# sapflow_v3.net
KiCad netlist of a schematic drawn in EAGLE
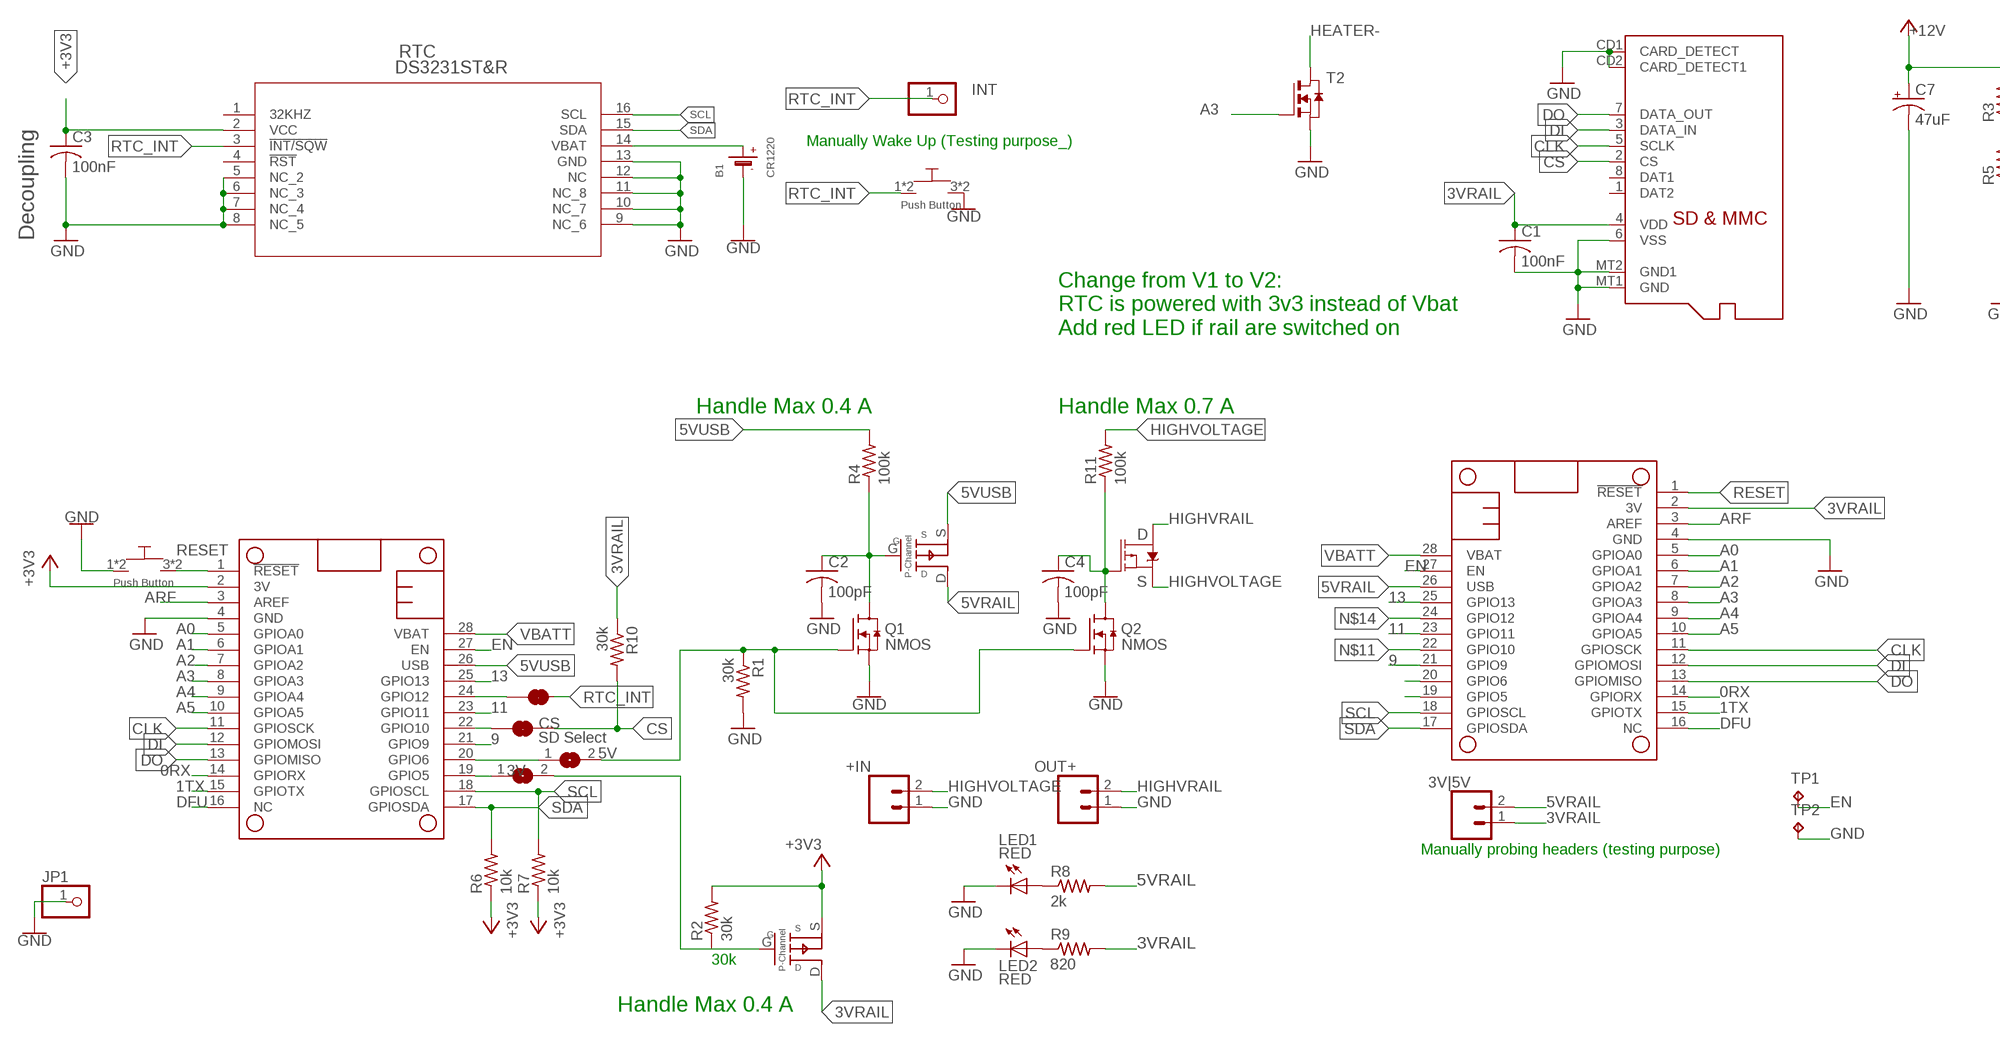
[diagram p0: schematic, sheet 1, part 1 of 2]
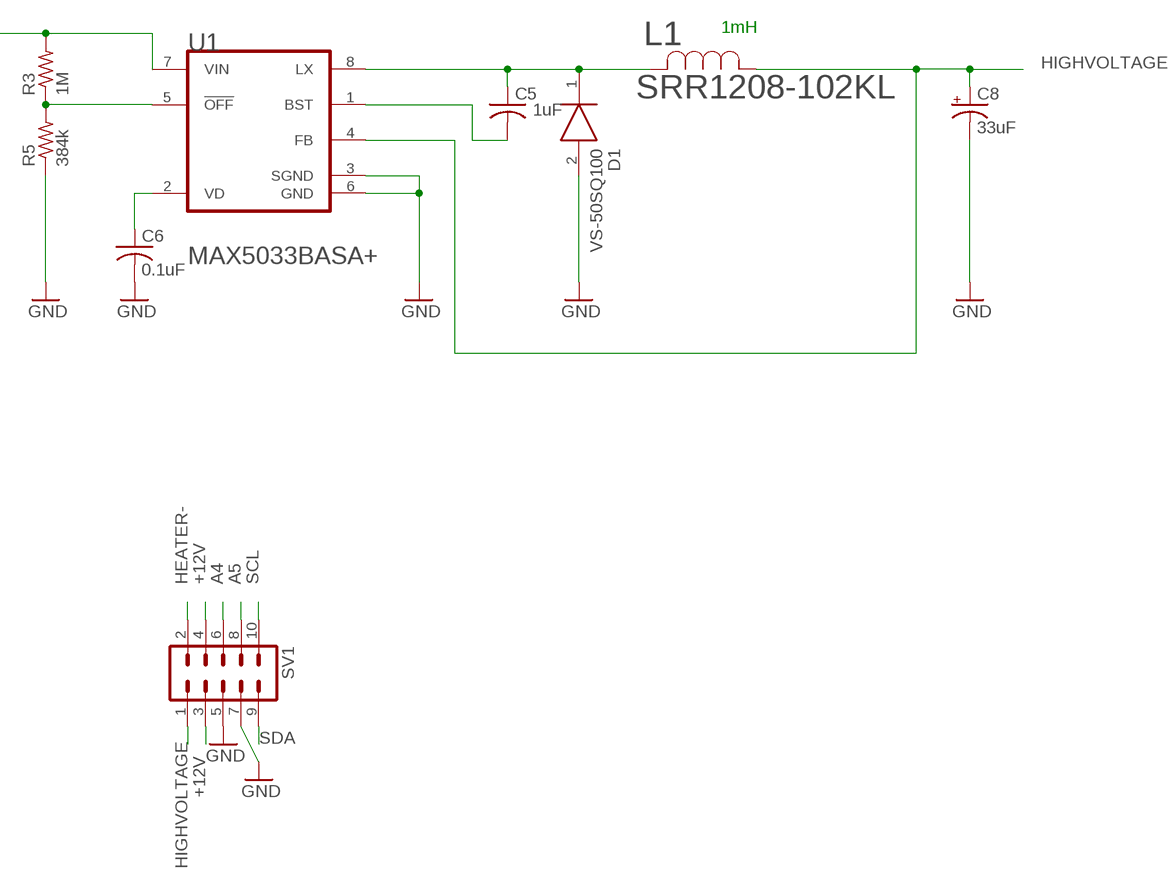
[diagram p1: schematic, sheet 1, part 2 of 2]

(export (version "E")
  (design (tool "Eeschema 10.0.6"))
  (components
    (comp (ref "+IN")
      (value "HIGHV-IN")
      (footprint "eagle-import:1X02_NO_SILK")
      (libsource (lib "eagle-import") (part "CONN_021X02_NO_SILK"))
    )
    (comp (ref "3V") (value "SJ") (footprint "eagle-import:SJ") (libsource (lib "eagle-import") (part "SJ")))
    (comp (ref "3V|5V")
      (value "CONN_021X02_NO_SILK")
      (footprint "eagle-import:1X02_NO_SILK")
      (libsource (lib "eagle-import") (part "CONN_021X02_NO_SILK"))
    )
    (comp (ref "5V") (value "SJ") (footprint "eagle-import:SJ") (libsource (lib "eagle-import") (part "SJ")))
    (comp (ref "B1")
      (value "CR1220")
      (footprint "eagle-import:CR1220")
      (libsource (lib "eagle-import") (part "BATTERYCR1220_SMT"))
    )
    (comp (ref "C1")
      (value "100nF")
      (footprint "eagle-import:C1206")
      (libsource (lib "eagle-import") (part "C-USC1206"))
    )
    (comp (ref "C2")
      (value "100pF")
      (footprint "eagle-import:C0805")
      (libsource (lib "eagle-import") (part "resistor_348_C-USC0805"))
    )
    (comp (ref "C3")
      (value "100nF")
      (footprint "eagle-import:C1206")
      (libsource (lib "eagle-import") (part "C-USC1206"))
    )
    (comp (ref "C4")
      (value "100pF")
      (footprint "eagle-import:C0805")
      (libsource (lib "eagle-import") (part "resistor_348_C-USC0805"))
    )
    (comp (ref "C5")
      (value "1uF")
      (footprint "eagle-import:C0603")
      (libsource (lib "eagle-import") (part "rcl_334_C-USC0603"))
    )
    (comp (ref "C6")
      (value "0.1uF")
      (footprint "eagle-import:C0603")
      (libsource (lib "eagle-import") (part "rcl_334_C-USC0603"))
    )
    (comp (ref "C7")
      (value "47uF")
      (footprint "eagle-import:D_7343-31R")
      (libsource (lib "eagle-import") (part "CPOL-USD/7343-31R"))
    )
    (comp (ref "C8")
      (value "33uF")
      (footprint "eagle-import:D_7343-31R")
      (libsource (lib "eagle-import") (part "CPOL-USD/7343-31R"))
    )
    (comp (ref "CS")
      (value "SD Select")
      (footprint "eagle-import:SMT-JUMPER_2_NC_TRACE_SILK")
      (libsource (lib "eagle-import") (part "JUMPER-SMT_2_NC_TRACE_SILK"))
    )
    (comp (ref "D1")
      (value "VS-50SQ100")
      (footprint "eagle-import:DIOAD1405W86L465D235")
      (fields (field (name "MOUSER_PART_NUMBER") "844-50SQ100") (field (name "RS_PART_NUMBER") "5446041"))
      (libsource (lib "eagle-import") (part "VS-50SQ100"))
    )
    (comp (ref "INT")
      (value "PINHD-1X1CB")
      (footprint "eagle-import:1X01-CLEANBIG")
      (libsource (lib "eagle-import") (part "PINHD-1X1CB"))
    )
    (comp (ref "JP1")
      (value "PINHD-1X1CB")
      (footprint "eagle-import:1X01-CLEANBIG")
      (libsource (lib "eagle-import") (part "PINHD-1X1CB"))
    )
    (comp (ref "L1")
      (value "SRR1208-102KL")
      (footprint "eagle-import:IND_BOURNS_SRR1208")
      (libsource (lib "eagle-import") (part "SRR1208-102KL"))
    )
    (comp (ref "LED1")
      (value "RED")
      (footprint "eagle-import:CHIPLED_0805")
      (libsource (lib "eagle-import") (part "LEDCHIPLED_0805"))
    )
    (comp (ref "LED2")
      (value "RED")
      (footprint "eagle-import:CHIPLED_0805")
      (libsource (lib "eagle-import") (part "LEDCHIPLED_0805"))
    )
    (comp (ref "MICROSD")
      (value "MICROSD")
      (footprint "eagle-import:MICROSD")
      (libsource (lib "eagle-import") (part "MICROSD"))
    )
    (comp (ref "MS1")
      (value "FEATHERWING")
      (footprint "eagle-import:FEATHERWING")
      (libsource (lib "eagle-import") (part "powerboard_FEATHERWING"))
    )
    (comp (ref "MS2")
      (value "FEATHERWING")
      (footprint "eagle-import:FEATHERWING")
      (libsource (lib "eagle-import") (part "FEATHERWING"))
    )
    (comp (ref "OUT+")
      (value "HIGHV-OUT")
      (footprint "eagle-import:1X02_NO_SILK")
      (libsource (lib "eagle-import") (part "CONN_021X02_NO_SILK"))
    )
    (comp (ref "PMOS1")
      (value "SSM3J3228R")
      (footprint "eagle-import:SOT-23-3")
      (libsource (lib "eagle-import") (part "SSM3J3228R"))
    )
    (comp (ref "PMOS2")
      (value "SSM3J3228R")
      (footprint "eagle-import:SOT-23-3")
      (libsource (lib "eagle-import") (part "SSM3J3228R"))
    )
    (comp (ref "PMOS3")
      (value "P-MOSFET")
      (footprint "eagle-import:SOT23-6")
      (libsource (lib "eagle-import") (part "P-MOSFET"))
    )
    (comp (ref "Q1")
      (value "NMOS")
      (footprint "eagle-import:SOT23-S")
      (libsource (lib "eagle-import") (part "NMOS"))
    )
    (comp (ref "Q2")
      (value "NMOS")
      (footprint "eagle-import:SOT23-S")
      (libsource (lib "eagle-import") (part "NMOS"))
    )
    (comp (ref "R1")
      (value "30k")
      (footprint "eagle-import:RES_1206")
      (fields
        (field (name "DIGIKEY_PART_NUMBER") "WSLP-.05TR-ND")
        (field (name "MANUFACTURER") "Vishay Dale")
        (field (name "MPN") "WSLP1206R0500FEA")
        (field (name "CREATED_BY") "PCBLayout.com")
      )
      (libsource (lib "eagle-import") (part "WSLP1206R0500FEA"))
    )
    (comp (ref "R2")
      (value "30k")
      (footprint "eagle-import:RES_1206")
      (fields
        (field (name "DIGIKEY_PART_NUMBER") "WSLP-.05TR-ND")
        (field (name "MANUFACTURER") "Vishay Dale")
        (field (name "MPN") "WSLP1206R0500FEA")
        (field (name "CREATED_BY") "PCBLayout.com")
      )
      (libsource (lib "eagle-import") (part "WSLP1206R0500FEA"))
    )
    (comp (ref "R3")
      (value "1M")
      (footprint "eagle-import:R0603")
      (libsource (lib "eagle-import") (part "R-US_R0603"))
    )
    (comp (ref "R4")
      (value "100k")
      (footprint "eagle-import:RES_1206")
      (fields
        (field (name "DIGIKEY_PART_NUMBER") "WSLP-.05TR-ND")
        (field (name "MANUFACTURER") "Vishay Dale")
        (field (name "MPN") "WSLP1206R0500FEA")
        (field (name "CREATED_BY") "PCBLayout.com")
      )
      (libsource (lib "eagle-import") (part "WSLP1206R0500FEA"))
    )
    (comp (ref "R5")
      (value "384k")
      (footprint "eagle-import:R0603")
      (libsource (lib "eagle-import") (part "R-US_R0603"))
    )
    (comp (ref "R6")
      (value "10k")
      (footprint "eagle-import:RES_1206")
      (fields
        (field (name "DIGIKEY_PART_NUMBER") "WSLP-.05TR-ND")
        (field (name "MANUFACTURER") "Vishay Dale")
        (field (name "MPN") "WSLP1206R0500FEA")
        (field (name "CREATED_BY") "PCBLayout.com")
      )
      (libsource (lib "eagle-import") (part "WSLP1206R0500FEA"))
    )
    (comp (ref "R7")
      (value "10k")
      (footprint "eagle-import:RES_1206")
      (fields
        (field (name "DIGIKEY_PART_NUMBER") "WSLP-.05TR-ND")
        (field (name "MANUFACTURER") "Vishay Dale")
        (field (name "MPN") "WSLP1206R0500FEA")
        (field (name "CREATED_BY") "PCBLayout.com")
      )
      (libsource (lib "eagle-import") (part "WSLP1206R0500FEA"))
    )
    (comp (ref "R8")
      (value "2k")
      (footprint "eagle-import:RES_1206")
      (fields
        (field (name "DIGIKEY_PART_NUMBER") "WSLP-.05TR-ND")
        (field (name "MANUFACTURER") "Vishay Dale")
        (field (name "MPN") "WSLP1206R0500FEA")
        (field (name "CREATED_BY") "PCBLayout.com")
      )
      (libsource (lib "eagle-import") (part "WSLP1206R0500FEA"))
    )
    (comp (ref "R9")
      (value "820")
      (footprint "eagle-import:RES_1206")
      (fields
        (field (name "DIGIKEY_PART_NUMBER") "WSLP-.05TR-ND")
        (field (name "MANUFACTURER") "Vishay Dale")
        (field (name "MPN") "WSLP1206R0500FEA")
        (field (name "CREATED_BY") "PCBLayout.com")
      )
      (libsource (lib "eagle-import") (part "WSLP1206R0500FEA"))
    )
    (comp (ref "R10")
      (value "30k")
      (footprint "eagle-import:RES_1206")
      (fields
        (field (name "DIGIKEY_PART_NUMBER") "WSLP-.05TR-ND")
        (field (name "MANUFACTURER") "Vishay Dale")
        (field (name "MPN") "WSLP1206R0500FEA")
        (field (name "CREATED_BY") "PCBLayout.com")
      )
      (libsource (lib "eagle-import") (part "WSLP1206R0500FEA"))
    )
    (comp (ref "R11")
      (value "100k")
      (footprint "eagle-import:RES_1206")
      (fields
        (field (name "DIGIKEY_PART_NUMBER") "WSLP-.05TR-ND")
        (field (name "MANUFACTURER") "Vishay Dale")
        (field (name "MPN") "WSLP1206R0500FEA")
        (field (name "CREATED_BY") "PCBLayout.com")
      )
      (libsource (lib "eagle-import") (part "WSLP1206R0500FEA"))
    )
    (comp (ref "RTC")
      (value "DS3231ST&R")
      (footprint "eagle-import:21-0042B_16")
      (fields (field (name "MANUFACTURER_PART_NUMBER") "DS3231S#T&R"))
      (libsource (lib "eagle-import") (part "DS3231ST&R"))
    )
    (comp (ref "RTC_INT")
      (value "JUMPER-SMT_2_NC_TRACE_SILK")
      (footprint "eagle-import:SMT-JUMPER_2_NC_TRACE_SILK")
      (libsource (lib "eagle-import") (part "JUMPER-SMT_2_NC_TRACE_SILK"))
    )
    (comp (ref "SV1")
      (value "MA05-2")
      (footprint "eagle-import:MA05-2")
      (libsource (lib "eagle-import") (part "MA05-2"))
    )
    (comp (ref "T2")
      (value "NMOSSOT223")
      (footprint "eagle-import:SOT223")
      (libsource (lib "eagle-import") (part "NMOSSOT223"))
    )
    (comp (ref "TP1")
      (value "TPTP16R")
      (footprint "eagle-import:TP16R")
      (libsource (lib "eagle-import") (part "TPTP16R"))
    )
    (comp (ref "TP2")
      (value "TPTP16R")
      (footprint "eagle-import:TP16R")
      (libsource (lib "eagle-import") (part "TPTP16R"))
    )
    (comp (ref "U$1")
      (value "PUSH_BUTTON")
      (footprint "eagle-import:PUSHBUTTON_SMD")
      (libsource (lib "eagle-import") (part "PUSH_BUTTON"))
    )
    (comp (ref "U$2")
      (value "PUSH_BUTTON")
      (footprint "eagle-import:PUSHBUTTON_SMD")
      (libsource (lib "eagle-import") (part "PUSH_BUTTON"))
    )
    (comp (ref "U1")
      (value "MAXIM_MAX5033BASA+MAXIM_MAX5033BASA+_0_1")
      (footprint "eagle-import:MAXIM_MAX5033BASA+_1")
      (fields (field (name "MF") "Maxim") (field (name "MPN") "MAX5033BASA+"))
      (libsource (lib "eagle-import") (part "MAXIM_MAX5033BASA+MAXIM_MAX5033BASA+_0_1"))
    )
  )
  (nets
    (net (code "1") (name "+3V3") (class "Default")
      (node (ref "C3") (pin "1") (pinfunction "1_1") (pintype "passive"))
      (node (ref "MS2") (pin "2") (pinfunction "3V_2") (pintype "power_in"))
      (node (ref "PMOS2") (pin "S") (pinfunction "S_S") (pintype "bidirectional"))
      (node (ref "R2") (pin "2") (pinfunction "2_2") (pintype "passive"))
      (node (ref "R6") (pin "1") (pinfunction "1_1") (pintype "passive"))
      (node (ref "R7") (pin "1") (pinfunction "1_1") (pintype "passive"))
      (node (ref "RTC") (pin "2") (pinfunction "VCC_2") (pintype "power_in"))
    )
    (net (code "2") (name "/0RX") (class "Default")
      (node (ref "MS1") (pin "14") (pinfunction "GPIORX_14") (pintype "bidirectional"))
      (node (ref "MS2") (pin "14") (pinfunction "GPIORX_14") (pintype "bidirectional"))
    )
    (net (code "3") (name "/1TX") (class "Default")
      (node (ref "MS1") (pin "15") (pinfunction "GPIOTX_15") (pintype "bidirectional"))
      (node (ref "MS2") (pin "15") (pinfunction "GPIOTX_15") (pintype "bidirectional"))
    )
    (net (code "4") (name "/9") (class "Default")
      (node (ref "MS1") (pin "21") (pinfunction "GPIO9_21") (pintype "bidirectional"))
      (node (ref "MS2") (pin "21") (pinfunction "GPIO9_21") (pintype "bidirectional"))
    )
    (net (code "5") (name "/11") (class "Default")
      (node (ref "MS1") (pin "23") (pinfunction "GPIO11_23") (pintype "bidirectional"))
      (node (ref "MS2") (pin "23") (pinfunction "GPIO11_23") (pintype "bidirectional"))
    )
    (net (code "6") (name "/13") (class "Default")
      (node (ref "MS1") (pin "25") (pinfunction "GPIO13_25") (pintype "bidirectional"))
      (node (ref "MS2") (pin "25") (pinfunction "GPIO13_25") (pintype "bidirectional"))
    )
    (net (code "7") (name "/A0") (class "Default")
      (node (ref "MS1") (pin "5") (pinfunction "GPIOA0_5") (pintype "bidirectional"))
      (node (ref "MS2") (pin "5") (pinfunction "GPIOA0_5") (pintype "bidirectional"))
    )
    (net (code "8") (name "/A1") (class "Default")
      (node (ref "MS1") (pin "6") (pinfunction "GPIOA1_6") (pintype "bidirectional"))
      (node (ref "MS2") (pin "6") (pinfunction "GPIOA1_6") (pintype "bidirectional"))
    )
    (net (code "9") (name "/A2") (class "Default")
      (node (ref "MS1") (pin "7") (pinfunction "GPIOA2_7") (pintype "bidirectional"))
      (node (ref "MS2") (pin "7") (pinfunction "GPIOA2_7") (pintype "bidirectional"))
    )
    (net (code "10") (name "/A3") (class "Default")
      (node (ref "MS1") (pin "8") (pinfunction "GPIOA3_8") (pintype "bidirectional"))
      (node (ref "MS2") (pin "8") (pinfunction "GPIOA3_8") (pintype "bidirectional"))
      (node (ref "T2") (pin "1") (pinfunction "G_1") (pintype "passive"))
    )
    (net (code "11") (name "/A4") (class "Default")
      (node (ref "MS1") (pin "9") (pinfunction "GPIOA4_9") (pintype "bidirectional"))
      (node (ref "MS2") (pin "9") (pinfunction "GPIOA4_9") (pintype "bidirectional"))
      (node (ref "SV1") (pin "6") (pinfunction "6_6") (pintype "passive"))
    )
    (net (code "12") (name "/A5") (class "Default")
      (node (ref "MS1") (pin "10") (pinfunction "GPIOA5_10") (pintype "bidirectional"))
      (node (ref "MS2") (pin "10") (pinfunction "GPIOA5_10") (pintype "bidirectional"))
      (node (ref "SV1") (pin "8") (pinfunction "8_8") (pintype "passive"))
    )
    (net (code "13") (name "/ARF") (class "Default")
      (node (ref "MS1") (pin "3") (pinfunction "AREF_3") (pintype "passive"))
      (node (ref "MS2") (pin "3") (pinfunction "AREF_3") (pintype "passive"))
    )
    (net (code "14") (name "/DFU") (class "Default")
      (node (ref "MS1") (pin "16") (pinfunction "NC_16") (pintype "passive"))
      (node (ref "MS2") (pin "16") (pinfunction "NC_16") (pintype "passive"))
    )
    (net (code "15") (name "/EN") (class "Default")
      (node (ref "MS1") (pin "27") (pinfunction "EN_27") (pintype "passive"))
      (node (ref "MS2") (pin "27") (pinfunction "EN_27") (pintype "passive"))
      (node (ref "TP1") (pin "TP") (pinfunction "TP_TP") (pintype "input"))
    )
    (net (code "16") (name "/HEATER-") (class "Default")
      (node (ref "SV1") (pin "2") (pinfunction "2_2") (pintype "passive"))
      (node (ref "T2") (pin "2") (pinfunction "D_2") (pintype "passive"))
      (node (ref "T2") (pin "4") (pinfunction "D_4") (pintype "passive"))
    )
    (net (code "17") (name "/HIGHVRAIL") (class "Default")
      (node (ref "OUT+") (pin "2") (pinfunction "2_2") (pintype "passive"))
      (node (ref "PMOS3") (pin "1") (pinfunction "D_1") (pintype "bidirectional"))
      (node (ref "PMOS3") (pin "2") (pinfunction "D_2") (pintype "bidirectional"))
      (node (ref "PMOS3") (pin "5") (pinfunction "D_5") (pintype "bidirectional"))
      (node (ref "PMOS3") (pin "6") (pinfunction "D_6") (pintype "bidirectional"))
    )
    (net (code "18") (name "3VRAIL") (class "Default")
      (node (ref "3V|5V") (pin "1") (pinfunction "1_1") (pintype "passive"))
      (node (ref "C1") (pin "1") (pinfunction "1_1") (pintype "passive"))
      (node (ref "MICROSD") (pin "4") (pinfunction "VDD_4") (pintype "power_in"))
      (node (ref "MS1") (pin "2") (pinfunction "3V_2") (pintype "power_in"))
      (node (ref "PMOS2") (pin "D") (pinfunction "D_D") (pintype "bidirectional"))
      (node (ref "R10") (pin "1") (pinfunction "1_1") (pintype "passive"))
      (node (ref "R9") (pin "2") (pinfunction "2_2") (pintype "passive"))
    )
    (net (code "19") (name "5VRAIL") (class "Default")
      (node (ref "3V|5V") (pin "2") (pinfunction "2_2") (pintype "passive"))
      (node (ref "MS1") (pin "26") (pinfunction "USB_26") (pintype "power_in"))
      (node (ref "PMOS1") (pin "D") (pinfunction "D_D") (pintype "bidirectional"))
      (node (ref "R8") (pin "2") (pinfunction "2_2") (pintype "passive"))
    )
    (net (code "20") (name "5VUSB") (class "Default")
      (node (ref "MS2") (pin "26") (pinfunction "USB_26") (pintype "power_in"))
      (node (ref "PMOS1") (pin "S") (pinfunction "S_S") (pintype "bidirectional"))
      (node (ref "R4") (pin "2") (pinfunction "2_2") (pintype "passive"))
    )
    (net (code "21") (name "15V") (class "Default")
      (node (ref "C7") (pin "+") (pinfunction "+_+") (pintype "passive"))
      (node (ref "R3") (pin "2") (pinfunction "2_2") (pintype "passive"))
      (node (ref "SV1") (pin "3") (pinfunction "3_3") (pintype "passive"))
      (node (ref "SV1") (pin "4") (pinfunction "4_4") (pintype "passive"))
      (node (ref "U1") (pin "7") (pinfunction "VIN_7") (pintype "power_in"))
    )
    (net (code "22") (name "CLK") (class "Default")
      (node (ref "MICROSD") (pin "5") (pinfunction "SCLK_5") (pintype "input"))
      (node (ref "MS1") (pin "11") (pinfunction "GPIOSCK_11") (pintype "bidirectional"))
      (node (ref "MS2") (pin "11") (pinfunction "GPIOSCK_11") (pintype "bidirectional"))
    )
    (net (code "23") (name "CS") (class "Default")
      (node (ref "CS") (pin "2") (pinfunction "2_2") (pintype "passive"))
      (node (ref "MICROSD") (pin "2") (pinfunction "CS_2") (pintype "input"))
      (node (ref "R10") (pin "2") (pinfunction "2_2") (pintype "passive"))
    )
    (net (code "24") (name "DI") (class "Default")
      (node (ref "MICROSD") (pin "3") (pinfunction "DATA_IN_3") (pintype "input"))
      (node (ref "MS1") (pin "12") (pinfunction "GPIOMOSI_12") (pintype "bidirectional"))
      (node (ref "MS2") (pin "12") (pinfunction "GPIOMOSI_12") (pintype "bidirectional"))
    )
    (net (code "25") (name "DO") (class "Default")
      (node (ref "MICROSD") (pin "7") (pinfunction "DATA_OUT_7") (pintype "output"))
      (node (ref "MS1") (pin "13") (pinfunction "GPIOMISO_13") (pintype "bidirectional"))
      (node (ref "MS2") (pin "13") (pinfunction "GPIOMISO_13") (pintype "bidirectional"))
    )
    (net (code "26") (name "GND") (class "Default")
      (node (ref "+IN") (pin "1") (pinfunction "1_1") (pintype "passive"))
      (node (ref "B1") (pin "-") (pinfunction "-_-") (pintype "passive"))
      (node (ref "C1") (pin "2") (pinfunction "2_2") (pintype "passive"))
      (node (ref "C2") (pin "2") (pinfunction "2_2") (pintype "passive"))
      (node (ref "C3") (pin "2") (pinfunction "2_2") (pintype "passive"))
      (node (ref "C4") (pin "2") (pinfunction "2_2") (pintype "passive"))
      (node (ref "C6") (pin "2") (pinfunction "2_2") (pintype "passive"))
      (node (ref "C7") (pin "-") (pinfunction "-_-") (pintype "passive"))
      (node (ref "C8") (pin "-") (pinfunction "-_-") (pintype "passive"))
      (node (ref "D1") (pin "2") (pinfunction "A_2") (pintype "bidirectional"))
      (node (ref "JP1") (pin "1") (pinfunction "1_1") (pintype "passive"))
      (node (ref "LED1") (pin "C") (pinfunction "C_C") (pintype "passive"))
      (node (ref "LED2") (pin "C") (pinfunction "C_C") (pintype "passive"))
      (node (ref "MICROSD") (pin "6") (pinfunction "VSS_6") (pintype "power_in"))
      (node (ref "MICROSD") (pin "CD1") (pinfunction "CARD_DETECT_CD1") (pintype "passive"))
      (node (ref "MICROSD") (pin "CD2") (pinfunction "CARD_DETECT1_CD2") (pintype "passive"))
      (node (ref "MICROSD") (pin "MT1") (pinfunction "GND_MT1") (pintype "power_in"))
      (node (ref "MICROSD") (pin "MT2") (pinfunction "GND1_MT2") (pintype "power_in"))
      (node (ref "MS1") (pin "4") (pinfunction "GND_4") (pintype "power_in"))
      (node (ref "MS2") (pin "4") (pinfunction "GND_4") (pintype "power_in"))
      (node (ref "OUT+") (pin "1") (pinfunction "1_1") (pintype "passive"))
      (node (ref "Q1") (pin "2") (pinfunction "S_2") (pintype "passive"))
      (node (ref "Q2") (pin "2") (pinfunction "S_2") (pintype "passive"))
      (node (ref "R1") (pin "2") (pinfunction "2_2") (pintype "passive"))
      (node (ref "R5") (pin "1") (pinfunction "1_1") (pintype "passive"))
      (node (ref "RTC") (pin "10") (pinfunction "NC_7_10") (pintype "passive"))
      (node (ref "RTC") (pin "11") (pinfunction "NC_8_11") (pintype "passive"))
      (node (ref "RTC") (pin "12") (pinfunction "NC_12") (pintype "passive"))
      (node (ref "RTC") (pin "13") (pinfunction "GND_13") (pintype "power_in"))
      (node (ref "RTC") (pin "5") (pinfunction "NC_2_5") (pintype "passive"))
      (node (ref "RTC") (pin "6") (pinfunction "NC_3_6") (pintype "passive"))
      (node (ref "RTC") (pin "7") (pinfunction "NC_4_7") (pintype "passive"))
      (node (ref "RTC") (pin "8") (pinfunction "NC_5_8") (pintype "passive"))
      (node (ref "RTC") (pin "9") (pinfunction "NC_6_9") (pintype "passive"))
      (node (ref "SV1") (pin "5") (pinfunction "5_5") (pintype "passive"))
      (node (ref "SV1") (pin "7") (pinfunction "7_7") (pintype "passive"))
      (node (ref "T2") (pin "3") (pinfunction "S_3") (pintype "passive"))
      (node (ref "TP2") (pin "TP") (pinfunction "TP_TP") (pintype "input"))
      (node (ref "U$1") (pin "1") (pinfunction "P$1_1") (pintype "bidirectional"))
      (node (ref "U$1") (pin "2") (pinfunction "P$1_2") (pintype "bidirectional"))
      (node (ref "U$2") (pin "3") (pinfunction "P$2_3") (pintype "bidirectional"))
      (node (ref "U$2") (pin "4") (pinfunction "P$2_4") (pintype "bidirectional"))
      (node (ref "U1") (pin "3") (pinfunction "SGND_3") (pintype "power_in"))
      (node (ref "U1") (pin "6") (pinfunction "GND_6") (pintype "power_in"))
    )
    (net (code "27") (name "HIGHVOLTAGE") (class "Default")
      (node (ref "+IN") (pin "2") (pinfunction "2_2") (pintype "passive"))
      (node (ref "C8") (pin "+") (pinfunction "+_+") (pintype "passive"))
      (node (ref "L1") (pin "1") (pinfunction "1_1") (pintype "passive"))
      (node (ref "PMOS3") (pin "4") (pinfunction "S_4") (pintype "bidirectional"))
      (node (ref "R11") (pin "2") (pinfunction "2_2") (pintype "passive"))
      (node (ref "SV1") (pin "1") (pinfunction "1_1") (pintype "passive"))
      (node (ref "U1") (pin "4") (pinfunction "FB_4") (pintype "input"))
    )
    (net (code "28") (name "N$11") (class "Default")
      (node (ref "CS") (pin "1") (pinfunction "1_1") (pintype "passive"))
      (node (ref "MS1") (pin "22") (pinfunction "GPIO10_22") (pintype "bidirectional"))
      (node (ref "MS2") (pin "22") (pinfunction "GPIO10_22") (pintype "bidirectional"))
    )
    (net (code "29") (name "N$14") (class "Default")
      (node (ref "MS1") (pin "24") (pinfunction "GPIO12_24") (pintype "bidirectional"))
      (node (ref "MS2") (pin "24") (pinfunction "GPIO12_24") (pintype "bidirectional"))
      (node (ref "RTC_INT") (pin "1") (pinfunction "1_1") (pintype "passive"))
    )
    (net (code "30") (name "Net-(3V-Pad2)") (class "Default")
      (node (ref "3V") (pin "2") (pinfunction "2_2") (pintype "passive"))
      (node (ref "PMOS2") (pin "G") (pinfunction "G_G") (pintype "bidirectional"))
      (node (ref "R2") (pin "1") (pinfunction "1_1") (pintype "passive"))
    )
    (net (code "31") (name "Net-(B1-+)") (class "Default")
      (node (ref "B1") (pin "+$1") (pinfunction "+_+$1") (pintype "passive"))
      (node (ref "RTC") (pin "14") (pinfunction "VBAT_14") (pintype "power_in"))
    )
    (net (code "32") (name "Net-(D1-K)") (class "Default")
      (node (ref "C5") (pin "1") (pinfunction "1_1") (pintype "passive"))
      (node (ref "D1") (pin "1") (pinfunction "K_1") (pintype "bidirectional"))
      (node (ref "L1") (pin "2") (pinfunction "2_2") (pintype "passive"))
      (node (ref "U1") (pin "8") (pinfunction "LX_8") (pintype "passive"))
    )
    (net (code "33") (name "Net-(LED1-PadA)") (class "Default")
      (node (ref "LED1") (pin "A") (pinfunction "A_A") (pintype "passive"))
      (node (ref "R8") (pin "1") (pinfunction "1_1") (pintype "passive"))
    )
    (net (code "34") (name "Net-(LED2-PadA)") (class "Default")
      (node (ref "LED2") (pin "A") (pinfunction "A_A") (pintype "passive"))
      (node (ref "R9") (pin "1") (pinfunction "1_1") (pintype "passive"))
    )
    (net (code "35") (name "Net-(MS2-GPIO5)") (class "Default")
      (node (ref "3V") (pin "1") (pinfunction "1_1") (pintype "passive"))
      (node (ref "MS2") (pin "19") (pinfunction "GPIO5_19") (pintype "bidirectional"))
    )
    (net (code "36") (name "Net-(MS2-GPIO6)") (class "Default")
      (node (ref "5V") (pin "1") (pinfunction "1_1") (pintype "passive"))
      (node (ref "MS2") (pin "20") (pinfunction "GPIO6_20") (pintype "bidirectional"))
    )
    (net (code "37") (name "Net-(PMOS3-G)") (class "Default")
      (node (ref "C4") (pin "1") (pinfunction "1_1") (pintype "passive"))
      (node (ref "PMOS3") (pin "3") (pinfunction "G_3") (pintype "bidirectional"))
      (node (ref "Q2") (pin "3") (pinfunction "D_3") (pintype "passive"))
      (node (ref "R11") (pin "1") (pinfunction "1_1") (pintype "passive"))
    )
    (net (code "38") (name "Net-(Q1-D)") (class "Default")
      (node (ref "C2") (pin "1") (pinfunction "1_1") (pintype "passive"))
      (node (ref "PMOS1") (pin "G") (pinfunction "G_G") (pintype "bidirectional"))
      (node (ref "Q1") (pin "3") (pinfunction "D_3") (pintype "passive"))
      (node (ref "R4") (pin "1") (pinfunction "1_1") (pintype "passive"))
    )
    (net (code "39") (name "Net-(Q1-G)") (class "Default")
      (node (ref "5V") (pin "2") (pinfunction "2_2") (pintype "passive"))
      (node (ref "Q1") (pin "1") (pinfunction "G_1") (pintype "passive"))
      (node (ref "Q2") (pin "1") (pinfunction "G_1") (pintype "passive"))
      (node (ref "R1") (pin "1") (pinfunction "1_1") (pintype "passive"))
    )
    (net (code "40") (name "Net-(U1-BST)") (class "Default")
      (node (ref "C5") (pin "2") (pinfunction "2_2") (pintype "passive"))
      (node (ref "U1") (pin "1") (pinfunction "BST_1") (pintype "passive"))
    )
    (net (code "41") (name "Net-(U1-VD)") (class "Default")
      (node (ref "C6") (pin "1") (pinfunction "1_1") (pintype "passive"))
      (node (ref "U1") (pin "2") (pinfunction "VD_2") (pintype "power_in"))
    )
    (net (code "42") (name "Net-(U1-~{OFF})") (class "Default")
      (node (ref "R3") (pin "1") (pinfunction "1_1") (pintype "passive"))
      (node (ref "R5") (pin "2") (pinfunction "2_2") (pintype "passive"))
      (node (ref "U1") (pin "5") (pinfunction "~{OFF}_5") (pintype "input"))
    )
    (net (code "43") (name "RESET") (class "Default")
      (node (ref "MS1") (pin "1") (pinfunction "~{RESET}_1") (pintype "input"))
      (node (ref "MS2") (pin "1") (pinfunction "~{RESET}_1") (pintype "input"))
      (node (ref "U$1") (pin "3") (pinfunction "P$2_3") (pintype "bidirectional"))
      (node (ref "U$1") (pin "4") (pinfunction "P$2_4") (pintype "bidirectional"))
    )
    (net (code "44") (name "RTC_INT") (class "Default")
      (node (ref "INT") (pin "1") (pinfunction "1_1") (pintype "passive"))
      (node (ref "RTC") (pin "3") (pinfunction "~{INT/SQW}_3") (pintype "passive"))
      (node (ref "RTC_INT") (pin "2") (pinfunction "2_2") (pintype "passive"))
      (node (ref "U$2") (pin "1") (pinfunction "P$1_1") (pintype "bidirectional"))
      (node (ref "U$2") (pin "2") (pinfunction "P$1_2") (pintype "bidirectional"))
    )
    (net (code "45") (name "SCL") (class "Default")
      (node (ref "MS1") (pin "18") (pinfunction "GPIOSCL_18") (pintype "bidirectional"))
      (node (ref "MS2") (pin "18") (pinfunction "GPIOSCL_18") (pintype "bidirectional"))
      (node (ref "R7") (pin "2") (pinfunction "2_2") (pintype "passive"))
      (node (ref "RTC") (pin "16") (pinfunction "SCL_16") (pintype "passive"))
      (node (ref "SV1") (pin "10") (pinfunction "10_10") (pintype "passive"))
    )
    (net (code "46") (name "SDA") (class "Default")
      (node (ref "MS1") (pin "17") (pinfunction "GPIOSDA_17") (pintype "bidirectional"))
      (node (ref "MS2") (pin "17") (pinfunction "GPIOSDA_17") (pintype "bidirectional"))
      (node (ref "R6") (pin "2") (pinfunction "2_2") (pintype "passive"))
      (node (ref "RTC") (pin "15") (pinfunction "SDA_15") (pintype "passive"))
      (node (ref "SV1") (pin "9") (pinfunction "9_9") (pintype "passive"))
    )
    (net (code "47") (name "VBATT") (class "Default")
      (node (ref "MS1") (pin "28") (pinfunction "VBAT_28") (pintype "power_in"))
      (node (ref "MS2") (pin "28") (pinfunction "VBAT_28") (pintype "power_in"))
    )
    (net (code "48") (name "unconnected-(MICROSD-DAT1-Pad8)") (class "Default")
      (node (ref "MICROSD") (pin "8") (pinfunction "DAT1_8") (pintype "bidirectional"))
    )
    (net (code "49") (name "unconnected-(MICROSD-DAT2-Pad1)") (class "Default")
      (node (ref "MICROSD") (pin "1") (pinfunction "DAT2_1") (pintype "bidirectional"))
    )
    (net (code "50") (name "unconnected-(MS1-GPIO5-Pad19)") (class "Default")
      (node (ref "MS1") (pin "19") (pinfunction "GPIO5_19") (pintype "bidirectional"))
    )
    (net (code "51") (name "unconnected-(MS1-GPIO6-Pad20)") (class "Default")
      (node (ref "MS1") (pin "20") (pinfunction "GPIO6_20") (pintype "bidirectional"))
    )
    (net (code "52") (name "unconnected-(RTC-32KHZ-Pad1)") (class "Default")
      (node (ref "RTC") (pin "1") (pinfunction "32KHZ_1") (pintype "passive"))
    )
    (net (code "53") (name "unconnected-(RTC-~{RST}-Pad4)") (class "Default")
      (node (ref "RTC") (pin "4") (pinfunction "~{RST}_4") (pintype "passive"))
    )
  )
)
